# AWG_CLK_Connectors.net
KiCad netlist of a schematic drawn in Altium Designer
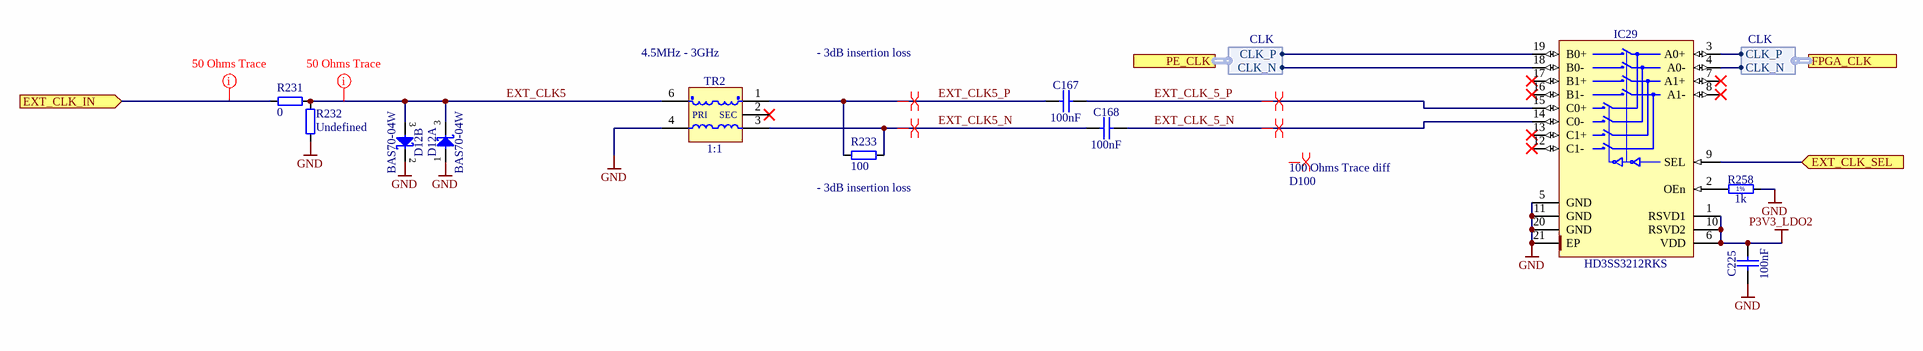
[diagram p0: AWG_CLK_Connectors.SchDoc]

(export (version "E")
  (design (tool "Eeschema 10.0.6"))
  (components
    (comp (ref "C167")
      (value "100nF")
      (footprint "CAPC0603X33N")
      (description "Non-polarised capacitor")
      (fields
        (field (name "PART NUMBER") "CC0201_100NF_6.3V_10%_X5R")
        (field (name "VOLTAGE") "6.3V")
        (field (name "AUTHOR") "CERN DEM JLC")
      )
      (libsource (lib "Capacitors") (part "Capacitor - non polarized"))
    )
    (comp (ref "C168")
      (value "100nF")
      (footprint "CAPC0603X33N")
      (description "Non-polarised capacitor")
      (fields
        (field (name "PART NUMBER") "CC0201_100NF_6.3V_10%_X5R")
        (field (name "VOLTAGE") "6.3V")
        (field (name "AUTHOR") "CERN DEM JLC")
      )
      (libsource (lib "Capacitors") (part "Capacitor - non polarized"))
    )
    (comp (ref "C225")
      (value "100nF")
      (footprint "CAPC1005X55N")
      (description "Non-polarised capacitor")
      (fields
        (field (name "PART NUMBER") "CC0402_100NF_16V_10%_X7R")
        (field (name "VOLTAGE") "16V")
        (field (name "AUTHOR") "CERN DEM JLC")
      )
      (libsource (lib "Capacitors") (part "Capacitor - non polarized"))
    )
    (comp (ref "D12")
      (value "BAS70-04W")
      (footprint "SOT65P210X110-3N")
      (description "Serial Schottky Diode")
      (fields
        (field (name "VOLTAGE") "70V")
        (field (name "POWER") "70mA")
        (field (name "AUTHOR") "CERN DEM JLC")
      )
      (libsource (lib "ICs And Semiconductors") (part "Diode Schottky x2 A1C3_A3C2"))
    )
    (comp (ref "IC29")
      (value "HD3SS3212RKS")
      (footprint "TEXAS_RKS0020A")
      (description "Two-Channel Differential 2:1/1:2 USB3.1 Mux/Demux")
      (fields (field (name "MANUFACTURER") "TEXAS INSTRUMENTS") (field (name "AUTHOR") "CERN DEM BC"))
      (libsource (lib "ICs And Semiconductors") (part "HD3SS3212RKS"))
    )
    (comp (ref "R231")
      (value "0")
      (footprint "RESC1005X40N")
      (description "Resistor")
      (fields
        (field (name "PART NUMBER") "R0402_0R_JUMPER")
        (field (name "MANUFACTURER") "GENERIC")
        (field (name "AUTHOR") "CERN DEM JLC")
      )
      (libsource (lib "Resistors") (part "Resistor"))
    )
    (comp (ref "R232")
      (value "Undefined")
      (footprint "RESC1005X40N")
      (description "Resistor")
      (fields (field (name "PART NUMBER") "R0402_NO-VALUE") (field (name "AUTHOR") "CERN DEM JLC"))
      (libsource (lib "Resistors") (part "Resistor"))
    )
    (comp (ref "R233")
      (value "100")
      (footprint "RESC1005X35N")
      (description "Resistor - 0.1%")
      (fields
        (field (name "TOLERANCE") "±0.1%")
        (field (name "PART NUMBER") "R0402_100R_0.1%_0.063W_25PPM")
        (field (name "AUTHOR") "CERN DEM JMW")
      )
      (libsource (lib "Resistors") (part "Resistor - 0.1%"))
    )
    (comp (ref "R258")
      (value "1k")
      (footprint "RESC1005X40N")
      (description "Resistor - 1%")
      (fields
        (field (name "PART NUMBER") "R0402_1K_1%_0.0625W_100PPM")
        (field (name "POWER") "0.0625W")
        (field (name "AUTHOR") "CERN DEM JLC")
      )
      (libsource (lib "Resistors") (part "Resistor - 1%"))
    )
    (comp (ref "TR2")
      (value "1:1")
      (footprint "XFMR_MINI-CIRCUITS_AT224")
      (description "50 Ohms 4.5 To 3000MHz RF Transformers")
      (fields
        (field (name "PART NUMBER") "XFMR_MINI-CIRCUITS_TC1-1-13M+")
        (field (name "MANUFACTURER") "MINI-CIRCUITS")
        (field (name "AUTHOR") "CERN DEM JLC")
      )
      (libsource (lib "Inductors & Transformers") (part "XFMR_MINI-CIRCUITS_TC1-1-13M+"))
    )
  )
  (nets
    (net (code "2") (name "/EXT_CLK5") (class "Default")
      (node (ref "D12") (pin "3") (pinfunction "COMAC_3") (pintype "passive"))
      (node (ref "R231") (pin "2") (pinfunction "2_2") (pintype "passive"))
      (node (ref "R232") (pin "1") (pinfunction "1_1") (pintype "passive"))
      (node (ref "TR2") (pin "6") (pinfunction "PDOT_6") (pintype "passive"))
    )
    (net (code "3") (name "/EXT_CLK5_N") (class "Default")
      (node (ref "C168") (pin "1") (pinfunction "1_1") (pintype "passive"))
      (node (ref "R233") (pin "2") (pinfunction "2_2") (pintype "passive"))
      (node (ref "TR2") (pin "3") (pinfunction "S_3") (pintype "passive"))
    )
    (net (code "4") (name "/EXT_CLK5_P") (class "Default")
      (node (ref "C167") (pin "1") (pinfunction "1_1") (pintype "passive"))
      (node (ref "R233") (pin "1") (pinfunction "1_1") (pintype "passive"))
      (node (ref "TR2") (pin "1") (pinfunction "SDOT_1") (pintype "passive"))
    )
    (net (code "5") (name "/EXT_CLK_5_N") (class "Default")
      (node (ref "C168") (pin "2") (pinfunction "2_2") (pintype "passive"))
      (node (ref "IC29") (pin "14") (pinfunction "C0-_14") (pintype "bidirectional"))
    )
    (net (code "6") (name "/EXT_CLK_5_P") (class "Default")
      (node (ref "C167") (pin "2") (pinfunction "2_2") (pintype "passive"))
      (node (ref "IC29") (pin "15") (pinfunction "C0+_15") (pintype "bidirectional"))
    )
    (net (code "7") (name "/EXT_CLK_IN") (class "Default")
      (node (ref "R231") (pin "1") (pinfunction "1_1") (pintype "passive"))
    )
    (net (code "8") (name "/EXT_CLK_SEL") (class "Default")
      (node (ref "IC29") (pin "9") (pinfunction "SEL_9") (pintype "input"))
    )
    (net (code "10") (name "GND") (class "Default")
      (node (ref "C225") (pin "1") (pinfunction "1_1") (pintype "passive"))
      (node (ref "D12") (pin "1") (pinfunction "A_1") (pintype "passive"))
      (node (ref "D12") (pin "2") (pinfunction "C_2") (pintype "passive"))
      (node (ref "IC29") (pin "11") (pinfunction "GND_11") (pintype "power_in"))
      (node (ref "IC29") (pin "20") (pinfunction "GND_20") (pintype "power_in"))
      (node (ref "IC29") (pin "21") (pinfunction "EP_21") (pintype "power_in"))
      (node (ref "IC29") (pin "5") (pinfunction "GND_5") (pintype "power_in"))
      (node (ref "R232") (pin "2") (pinfunction "2_2") (pintype "passive"))
      (node (ref "R258") (pin "2") (pinfunction "2_2") (pintype "passive"))
      (node (ref "TR2") (pin "4") (pinfunction "P_4") (pintype "passive"))
    )
    (net (code "11") (name "Net-(IC29-OEn)") (class "Default")
      (node (ref "IC29") (pin "2") (pinfunction "OEn_2") (pintype "input"))
      (node (ref "R258") (pin "1") (pinfunction "1_1") (pintype "passive"))
    )
    (net (code "12") (name "P3V3_LDO2") (class "Default")
      (node (ref "C225") (pin "2") (pinfunction "2_2") (pintype "passive"))
      (node (ref "IC29") (pin "1") (pinfunction "RSVD1_1") (pintype "power_in"))
      (node (ref "IC29") (pin "10") (pinfunction "RSVD2_10") (pintype "power_in"))
      (node (ref "IC29") (pin "6") (pinfunction "VDD_6") (pintype "power_in"))
    )
    (net (code "13") (name "unconnected-(IC29-A0+-Pad3)") (class "Default")
      (node (ref "IC29") (pin "3") (pinfunction "A0+_3") (pintype "bidirectional"))
    )
    (net (code "14") (name "unconnected-(IC29-A0--Pad4)") (class "Default")
      (node (ref "IC29") (pin "4") (pinfunction "A0-_4") (pintype "bidirectional"))
    )
    (net (code "15") (name "unconnected-(IC29-A1+-Pad7)") (class "Default")
      (node (ref "IC29") (pin "7") (pinfunction "A1+_7") (pintype "bidirectional+no_connect"))
    )
    (net (code "16") (name "unconnected-(IC29-A1--Pad8)") (class "Default")
      (node (ref "IC29") (pin "8") (pinfunction "A1-_8") (pintype "bidirectional+no_connect"))
    )
    (net (code "17") (name "unconnected-(IC29-B0+-Pad19)") (class "Default")
      (node (ref "IC29") (pin "19") (pinfunction "B0+_19") (pintype "bidirectional"))
    )
    (net (code "18") (name "unconnected-(IC29-B0--Pad18)") (class "Default")
      (node (ref "IC29") (pin "18") (pinfunction "B0-_18") (pintype "bidirectional"))
    )
    (net (code "19") (name "unconnected-(IC29-B1+-Pad17)") (class "Default")
      (node (ref "IC29") (pin "17") (pinfunction "B1+_17") (pintype "bidirectional+no_connect"))
    )
    (net (code "20") (name "unconnected-(IC29-B1--Pad16)") (class "Default")
      (node (ref "IC29") (pin "16") (pinfunction "B1-_16") (pintype "bidirectional+no_connect"))
    )
    (net (code "21") (name "unconnected-(IC29-C1+-Pad13)") (class "Default")
      (node (ref "IC29") (pin "13") (pinfunction "C1+_13") (pintype "bidirectional+no_connect"))
    )
    (net (code "22") (name "unconnected-(IC29-C1--Pad12)") (class "Default")
      (node (ref "IC29") (pin "12") (pinfunction "C1-_12") (pintype "bidirectional+no_connect"))
    )
    (net (code "23") (name "unconnected-(TR2-NC-Pad2)") (class "Default")
      (node (ref "TR2") (pin "2") (pinfunction "NC_2") (pintype "passive+no_connect"))
    )
  )
)
